# 1-Schematic_Sprinkler.net
KiCad netlist of a schematic drawn in EasyEDA
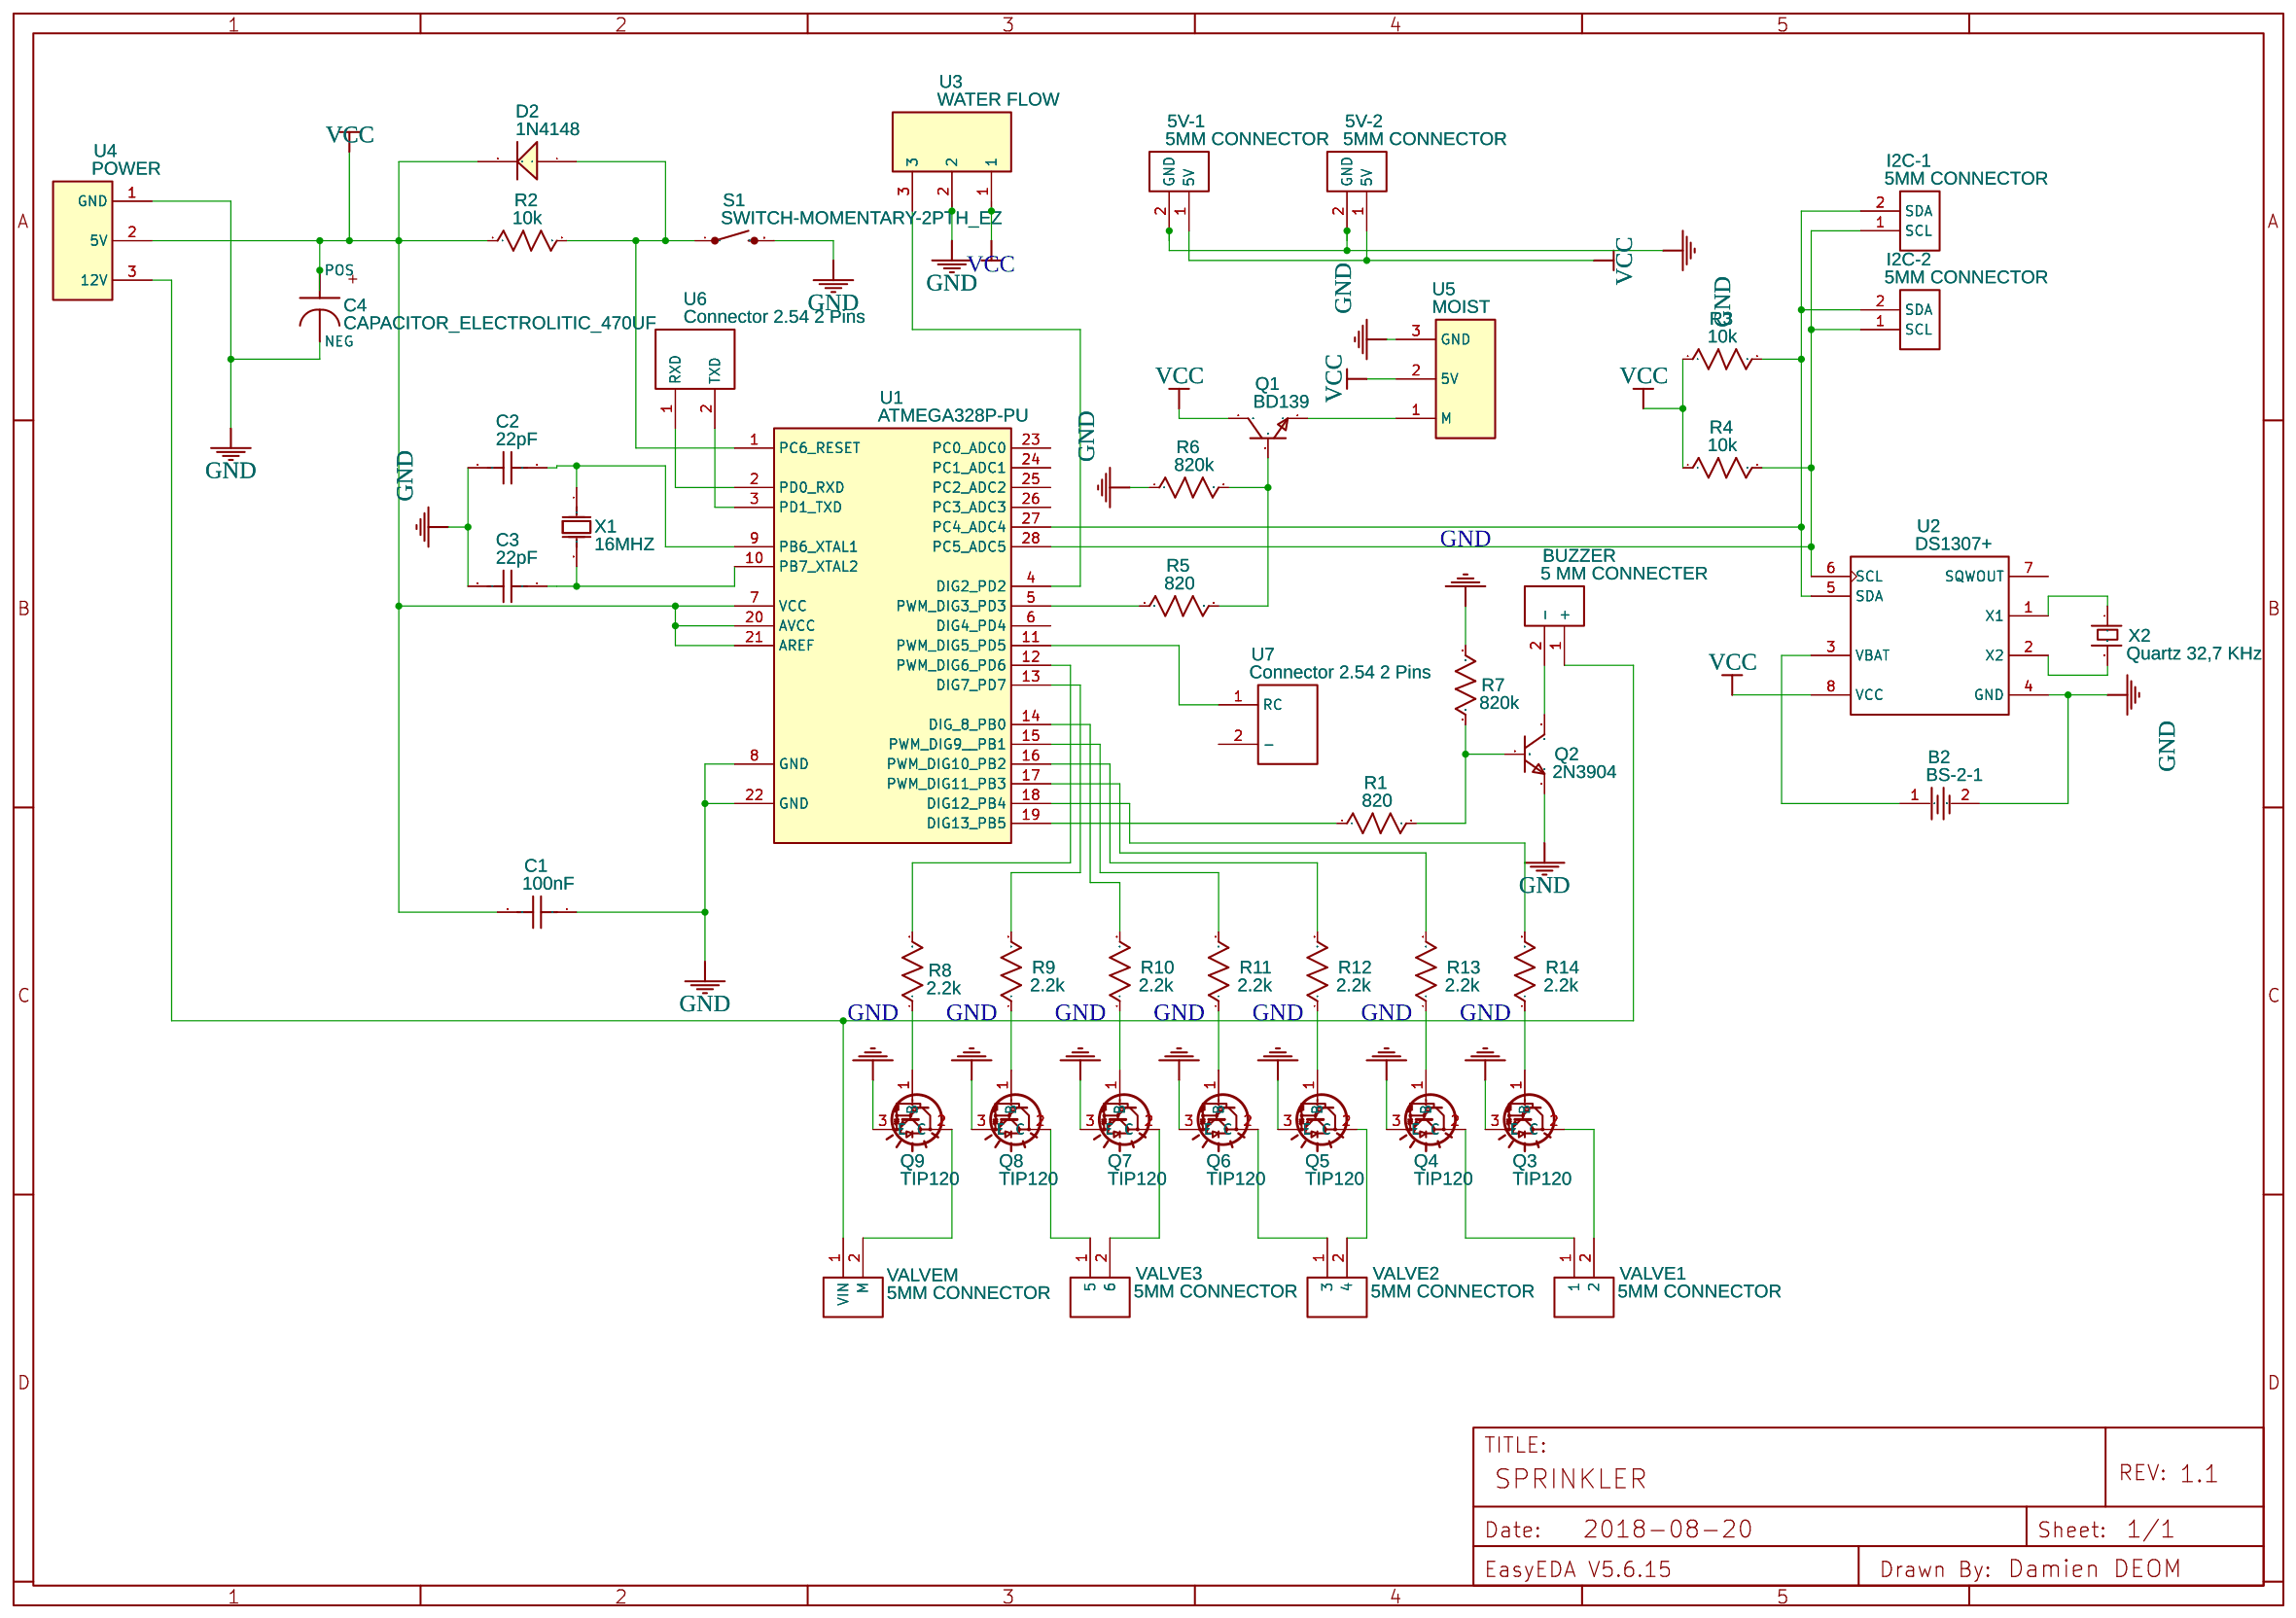
[diagram p0: schematic sheet]

(export (version "E")
  (design (tool "Eeschema 10.0.6"))
  (components
    (comp (ref "5V-1") (value "5MM CONNECTOR") (libsource (lib "") (part "Unknown_575_70")))
    (comp (ref "5V-2") (value "5MM CONNECTOR") (libsource (lib "") (part "Unknown_665_70")))
    (comp (ref "B2")
      (value "BS-2-1")
      (fields (field (name "BOM_Supplier Part") "C70376"))
      (libsource (lib "") (part "Unknown_975_400"))
    )
    (comp (ref "BUZZER")
      (value "5 MM CONNECTER")
      (fields (field (name "BOM_Manufacturer Part") "5MM CONNECTOR"))
      (libsource (lib "") (part "Unknown_765_290"))
    )
    (comp (ref "C1")
      (value "100nF")
      (fields (field (name "BOM_Manufacturer Part") "?"))
      (libsource (lib "") (part "Cap_RAD-0.1_US"))
    )
    (comp (ref "C2")
      (value "22pF")
      (fields (field (name "BOM_Manufacturer Part") "?"))
      (libsource (lib "") (part "Cap_RAD-0.1_US"))
    )
    (comp (ref "C3")
      (value "22pF")
      (fields (field (name "BOM_Manufacturer Part") "?"))
      (libsource (lib "") (part "Cap_RAD-0.1_US"))
    )
    (comp (ref "C4")
      (value "CAPACITOR_ELECTROLITIC_470UF")
      (fields (field (name "BOM_Manufacturer Part") "?"))
      (libsource (lib "") (part "Unknown_155_130"))
    )
    (comp (ref "D2")
      (value "1N4148")
      (fields (field (name "BOM_Manufacturer Part") "?"))
      (libsource (lib "") (part "Unknown_265_75"))
    )
    (comp (ref "I2C-1") (value "5MM CONNECTOR") (libsource (lib "") (part "Unknown_975_90")))
    (comp (ref "I2C-2") (value "5MM CONNECTOR") (libsource (lib "") (part "Unknown_975_140")))
    (comp (ref "Q1")
      (value "BD139")
      (fields (field (name "BOM_Supplier Part") "C27866"))
      (libsource (lib "") (part "Unknown_635_205"))
    )
    (comp (ref "Q2")
      (value "2N3904")
      (fields (field (name "BOM_Supplier Part") "C118538"))
      (libsource (lib "") (part "Unknown_765_375"))
    )
    (comp (ref "Q3")
      (value "TIP120")
      (fields (field (name "BOM_Manufacturer Part") "?"))
      (libsource (lib "") (part "Unknown_765_550"))
    )
    (comp (ref "Q4")
      (value "TIP120")
      (fields (field (name "BOM_Manufacturer Part") "?"))
      (libsource (lib "") (part "Unknown_715_550"))
    )
    (comp (ref "Q5")
      (value "TIP120")
      (fields (field (name "BOM_Manufacturer Part") "?"))
      (libsource (lib "") (part "Unknown_660_550"))
    )
    (comp (ref "Q6")
      (value "TIP120")
      (fields (field (name "BOM_Manufacturer Part") "?"))
      (libsource (lib "") (part "Unknown_610_550"))
    )
    (comp (ref "Q7")
      (value "TIP120")
      (fields (field (name "BOM_Manufacturer Part") "?"))
      (libsource (lib "") (part "Unknown_560_550"))
    )
    (comp (ref "Q8")
      (value "TIP120")
      (fields (field (name "BOM_Manufacturer Part") "?"))
      (libsource (lib "") (part "Unknown_505_550"))
    )
    (comp (ref "Q9")
      (value "TIP120")
      (fields (field (name "BOM_Manufacturer Part") "?"))
      (libsource (lib "") (part "Unknown_455_550"))
    )
    (comp (ref "R1")
      (value "820")
      (fields (field (name "BOM_Manufacturer Part") "?"))
      (libsource (lib "") (part "Res_AXIAL-0.3(1/8W)_US_1"))
    )
    (comp (ref "R2")
      (value "10k")
      (fields (field (name "BOM_Manufacturer Part") "?"))
      (libsource (lib "") (part "Res_AXIAL-0.3(1/8W)_US_1"))
    )
    (comp (ref "R3")
      (value "10k")
      (fields (field (name "BOM_Manufacturer Part") "?"))
      (libsource (lib "") (part "Res_AXIAL-0.3(1/8W)_US_1"))
    )
    (comp (ref "R4")
      (value "10k")
      (fields (field (name "BOM_Manufacturer Part") "?"))
      (libsource (lib "") (part "Res_AXIAL-0.3(1/8W)_US_1"))
    )
    (comp (ref "R5")
      (value "820")
      (fields (field (name "BOM_Manufacturer Part") "?"))
      (libsource (lib "") (part "Res_AXIAL-0.3(1/8W)_US_1"))
    )
    (comp (ref "R6")
      (value "820k")
      (fields (field (name "BOM_Manufacturer Part") "?"))
      (libsource (lib "") (part "Res_AXIAL-0.3(1/8W)_US_1"))
    )
    (comp (ref "R7")
      (value "820k")
      (fields (field (name "BOM_Manufacturer Part") "?"))
      (libsource (lib "") (part "Res_AXIAL-0.3(1/8W)_US"))
    )
    (comp (ref "R8")
      (value "2.2k")
      (fields (field (name "BOM_Manufacturer Part") "?"))
      (libsource (lib "") (part "Res_AXIAL-0.3(1/8W)_US"))
    )
    (comp (ref "R9")
      (value "2.2k")
      (fields (field (name "BOM_Manufacturer Part") "?"))
      (libsource (lib "") (part "Res_AXIAL-0.3(1/8W)_US"))
    )
    (comp (ref "R10")
      (value "2.2k")
      (fields (field (name "BOM_Manufacturer Part") "?"))
      (libsource (lib "") (part "Res_AXIAL-0.3(1/8W)_US"))
    )
    (comp (ref "R11")
      (value "2.2k")
      (fields (field (name "BOM_Manufacturer Part") "?"))
      (libsource (lib "") (part "Res_AXIAL-0.3(1/8W)_US"))
    )
    (comp (ref "R12")
      (value "2.2k")
      (fields (field (name "BOM_Manufacturer Part") "?"))
      (libsource (lib "") (part "Res_AXIAL-0.3(1/8W)_US"))
    )
    (comp (ref "R13")
      (value "2.2k")
      (fields (field (name "BOM_Manufacturer Part") "?"))
      (libsource (lib "") (part "Res_AXIAL-0.3(1/8W)_US"))
    )
    (comp (ref "R14")
      (value "2.2k")
      (fields (field (name "BOM_Manufacturer Part") "?"))
      (libsource (lib "") (part "Res_AXIAL-0.3(1/8W)_US"))
    )
    (comp (ref "S1")
      (value "SWITCH-MOMENTARY-2PTH_EZ")
      (fields (field (name "BOM_Manufacturer Part") "?"))
      (libsource (lib "") (part "Unknown_365_115"))
    )
    (comp (ref "U1")
      (value "ATMEGA328P-PU")
      (fields (field (name "BOM_Supplier Part") "C33901"))
      (libsource (lib "") (part "Unknown_425_340"))
    )
    (comp (ref "U2")
      (value "DS1307+")
      (fields (field (name "BOM_Supplier Part") "C59267"))
      (libsource (lib "") (part "Unknown_970_315"))
    )
    (comp (ref "U3")
      (value "WATER FLOW")
      (fields (field (name "BOM_Manufacturer Part") "New SchematicLib"))
      (libsource (lib "") (part "Unknown_485_110"))
    )
    (comp (ref "U4")
      (value "POWER")
      (fields (field (name "BOM_Manufacturer Part") "New SchematicLib"))
      (libsource (lib "") (part "Unknown_80_105"))
    )
    (comp (ref "U5")
      (value "MOIST")
      (fields (field (name "BOM_Manufacturer Part") "New SchematicLib"))
      (libsource (lib "") (part "Unknown_690_195"))
    )
    (comp (ref "U6")
      (value "Connector 2.54 2 Pins")
      (fields (field (name "BOM_Manufacturer Part") "New SchematicLib"))
      (libsource (lib "") (part "Unknown_345_190"))
    )
    (comp (ref "U7")
      (value "Connector 2.54 2 Pins")
      (fields (field (name "BOM_Manufacturer Part") "New SchematicLib"))
      (libsource (lib "") (part "Unknown_630_360"))
    )
    (comp (ref "VALVE1") (value "5MM CONNECTOR") (libsource (lib "") (part "Unknown_810_660")))
    (comp (ref "VALVE2") (value "5MM CONNECTOR") (libsource (lib "") (part "Unknown_685_660")))
    (comp (ref "VALVE3") (value "5MM CONNECTOR") (libsource (lib "") (part "Unknown_565_660")))
    (comp (ref "VALVEM") (value "5MM CONNECTOR") (libsource (lib "") (part "Unknown_440_660")))
    (comp (ref "X1")
      (value "16MHZ")
      (fields
        (field (name "BOM_Manufacturer Part") "X49SD16MSD2SC")
        (field (name "BOM_Supplier Part") "C16212")
      )
      (libsource (lib "") (part "Unknown_285_260"))
    )
    (comp (ref "X2")
      (value "Quartz 32,7 KHz")
      (fields (field (name "BOM_Manufacturer Part") "?"))
      (libsource (lib "") (part "Unknown_1060_315"))
    )
  )
  (nets
    (net (code "1") (name "GND") (class "Default")
      (node (ref "5V-1") (pin "2") (pinfunction "GND_2") (pintype "unspecified"))
      (node (ref "5V-2") (pin "2") (pinfunction "GND_2") (pintype "unspecified"))
      (node (ref "B2") (pin "2") (pinfunction "2_2") (pintype "input"))
      (node (ref "C1") (pin "1") (pinfunction "1_1") (pintype "unspecified"))
      (node (ref "C2") (pin "2") (pinfunction "2_2") (pintype "unspecified"))
      (node (ref "C3") (pin "2") (pinfunction "2_2") (pintype "unspecified"))
      (node (ref "C4") (pin "NEG") (pinfunction "NEG_NEG") (pintype "bidirectional"))
      (node (ref "Q2") (pin "1") (pinfunction "E_1") (pintype "unspecified"))
      (node (ref "Q3") (pin "3") (pinfunction "E_3") (pintype "unspecified"))
      (node (ref "Q4") (pin "3") (pinfunction "E_3") (pintype "unspecified"))
      (node (ref "Q5") (pin "3") (pinfunction "E_3") (pintype "unspecified"))
      (node (ref "Q6") (pin "3") (pinfunction "E_3") (pintype "unspecified"))
      (node (ref "Q7") (pin "3") (pinfunction "E_3") (pintype "unspecified"))
      (node (ref "Q8") (pin "3") (pinfunction "E_3") (pintype "unspecified"))
      (node (ref "Q9") (pin "3") (pinfunction "E_3") (pintype "unspecified"))
      (node (ref "R6") (pin "1") (pinfunction "1_1") (pintype "unspecified"))
      (node (ref "R7") (pin "2") (pinfunction "2_2") (pintype "unspecified"))
      (node (ref "S1") (pin "3") (pinfunction "2_3") (pintype "unspecified"))
      (node (ref "U1") (pin "22") (pinfunction "GND_22") (pintype "passive"))
      (node (ref "U1") (pin "8") (pinfunction "GND_8") (pintype "passive"))
      (node (ref "U2") (pin "4") (pinfunction "GND_4") (pintype "passive"))
      (node (ref "U3") (pin "2") (pinfunction "2_2") (pintype "input"))
      (node (ref "U4") (pin "1") (pinfunction "GND_1") (pintype "input"))
      (node (ref "U5") (pin "3") (pinfunction "GND_3") (pintype "input"))
    )
    (net (code "2") (name "Net-(BUZZER-+)") (class "Default")
      (node (ref "BUZZER") (pin "1") (pinfunction "+_1") (pintype "unspecified"))
      (node (ref "U4") (pin "3") (pinfunction "12V_3") (pintype "input"))
      (node (ref "VALVEM") (pin "1") (pinfunction "VIN_1") (pintype "unspecified"))
    )
    (net (code "3") (name "Net-(BUZZER--)") (class "Default")
      (node (ref "BUZZER") (pin "2") (pinfunction "-_2") (pintype "unspecified"))
      (node (ref "Q2") (pin "3") (pinfunction "C_3") (pintype "unspecified"))
    )
    (net (code "4") (name "Net-(D2-A)") (class "Default")
      (node (ref "D2") (pin "1") (pinfunction "A_1") (pintype "unspecified"))
      (node (ref "R2") (pin "2") (pinfunction "2_2") (pintype "unspecified"))
      (node (ref "S1") (pin "1") (pinfunction "1_1") (pintype "unspecified"))
      (node (ref "U1") (pin "1") (pinfunction "PC6_RESET_1") (pintype "bidirectional"))
    )
    (net (code "5") (name "Net-(I2C-1-SCL)") (class "Default")
      (node (ref "I2C-1") (pin "1") (pinfunction "SCL_1") (pintype "unspecified"))
      (node (ref "I2C-2") (pin "1") (pinfunction "SCL_1") (pintype "unspecified"))
      (node (ref "R4") (pin "2") (pinfunction "2_2") (pintype "unspecified"))
      (node (ref "U1") (pin "28") (pinfunction "PC5_ADC5_28") (pintype "bidirectional"))
      (node (ref "U2") (pin "6") (pinfunction "SCL_6") (pintype "unspecified"))
    )
    (net (code "6") (name "Net-(I2C-1-SDA)") (class "Default")
      (node (ref "I2C-1") (pin "2") (pinfunction "SDA_2") (pintype "unspecified"))
      (node (ref "I2C-2") (pin "2") (pinfunction "SDA_2") (pintype "unspecified"))
      (node (ref "R3") (pin "2") (pinfunction "2_2") (pintype "unspecified"))
      (node (ref "U1") (pin "27") (pinfunction "PC4_ADC4_27") (pintype "bidirectional"))
      (node (ref "U2") (pin "5") (pinfunction "SDA_5") (pintype "bidirectional"))
    )
    (net (code "7") (name "Net-(Q1-B)") (class "Default")
      (node (ref "Q1") (pin "1") (pinfunction "B_1") (pintype "unspecified"))
      (node (ref "R5") (pin "2") (pinfunction "2_2") (pintype "unspecified"))
      (node (ref "R6") (pin "2") (pinfunction "2_2") (pintype "unspecified"))
    )
    (net (code "8") (name "Net-(Q1-E)") (class "Default")
      (node (ref "Q1") (pin "3") (pinfunction "E_3") (pintype "unspecified"))
      (node (ref "U5") (pin "1") (pinfunction "M_1") (pintype "input"))
    )
    (net (code "9") (name "Net-(Q2-B)") (class "Default")
      (node (ref "Q2") (pin "2") (pinfunction "B_2") (pintype "unspecified"))
      (node (ref "R1") (pin "2") (pinfunction "2_2") (pintype "unspecified"))
      (node (ref "R7") (pin "1") (pinfunction "1_1") (pintype "unspecified"))
    )
    (net (code "10") (name "Net-(Q3-B)") (class "Default")
      (node (ref "Q3") (pin "1") (pinfunction "B_1") (pintype "input"))
      (node (ref "R14") (pin "1") (pinfunction "1_1") (pintype "unspecified"))
    )
    (net (code "11") (name "Net-(Q3-C)") (class "Default")
      (node (ref "Q3") (pin "2") (pinfunction "C_2") (pintype "unspecified"))
      (node (ref "VALVE1") (pin "2") (pinfunction "2_2") (pintype "unspecified"))
    )
    (net (code "12") (name "Net-(Q4-B)") (class "Default")
      (node (ref "Q4") (pin "1") (pinfunction "B_1") (pintype "input"))
      (node (ref "R13") (pin "1") (pinfunction "1_1") (pintype "unspecified"))
    )
    (net (code "13") (name "Net-(Q4-C)") (class "Default")
      (node (ref "Q4") (pin "2") (pinfunction "C_2") (pintype "unspecified"))
      (node (ref "VALVE1") (pin "1") (pinfunction "1_1") (pintype "unspecified"))
    )
    (net (code "14") (name "Net-(Q5-B)") (class "Default")
      (node (ref "Q5") (pin "1") (pinfunction "B_1") (pintype "input"))
      (node (ref "R12") (pin "1") (pinfunction "1_1") (pintype "unspecified"))
    )
    (net (code "15") (name "Net-(Q5-C)") (class "Default")
      (node (ref "Q5") (pin "2") (pinfunction "C_2") (pintype "unspecified"))
      (node (ref "VALVE2") (pin "2") (pinfunction "4_2") (pintype "unspecified"))
    )
    (net (code "16") (name "Net-(Q6-B)") (class "Default")
      (node (ref "Q6") (pin "1") (pinfunction "B_1") (pintype "input"))
      (node (ref "R11") (pin "1") (pinfunction "1_1") (pintype "unspecified"))
    )
    (net (code "17") (name "Net-(Q6-C)") (class "Default")
      (node (ref "Q6") (pin "2") (pinfunction "C_2") (pintype "unspecified"))
      (node (ref "VALVE2") (pin "1") (pinfunction "3_1") (pintype "unspecified"))
    )
    (net (code "18") (name "Net-(Q7-B)") (class "Default")
      (node (ref "Q7") (pin "1") (pinfunction "B_1") (pintype "input"))
      (node (ref "R10") (pin "1") (pinfunction "1_1") (pintype "unspecified"))
    )
    (net (code "19") (name "Net-(Q7-C)") (class "Default")
      (node (ref "Q7") (pin "2") (pinfunction "C_2") (pintype "unspecified"))
      (node (ref "VALVE3") (pin "2") (pinfunction "6_2") (pintype "unspecified"))
    )
    (net (code "20") (name "Net-(Q8-B)") (class "Default")
      (node (ref "Q8") (pin "1") (pinfunction "B_1") (pintype "input"))
      (node (ref "R9") (pin "1") (pinfunction "1_1") (pintype "unspecified"))
    )
    (net (code "21") (name "Net-(Q8-C)") (class "Default")
      (node (ref "Q8") (pin "2") (pinfunction "C_2") (pintype "unspecified"))
      (node (ref "VALVE3") (pin "1") (pinfunction "5_1") (pintype "unspecified"))
    )
    (net (code "22") (name "Net-(Q9-B)") (class "Default")
      (node (ref "Q9") (pin "1") (pinfunction "B_1") (pintype "input"))
      (node (ref "R8") (pin "1") (pinfunction "1_1") (pintype "unspecified"))
    )
    (net (code "23") (name "Net-(Q9-C)") (class "Default")
      (node (ref "Q9") (pin "2") (pinfunction "C_2") (pintype "unspecified"))
      (node (ref "VALVEM") (pin "2") (pinfunction "M_2") (pintype "unspecified"))
    )
    (net (code "24") (name "Net-(U1-DIG2_PD2)") (class "Default")
      (node (ref "U1") (pin "4") (pinfunction "DIG2_PD2_4") (pintype "bidirectional"))
      (node (ref "U3") (pin "3") (pinfunction "3_3") (pintype "input"))
    )
    (net (code "25") (name "Net-(U1-DIG7_PD7)") (class "Default")
      (node (ref "R9") (pin "2") (pinfunction "2_2") (pintype "unspecified"))
      (node (ref "U1") (pin "13") (pinfunction "DIG7_PD7_13") (pintype "bidirectional"))
    )
    (net (code "26") (name "Net-(U1-DIG12_PB4)") (class "Default")
      (node (ref "R14") (pin "2") (pinfunction "2_2") (pintype "unspecified"))
      (node (ref "U1") (pin "18") (pinfunction "DIG12_PB4_18") (pintype "bidirectional"))
    )
    (net (code "27") (name "Net-(U1-DIG13_PB5)") (class "Default")
      (node (ref "R1") (pin "1") (pinfunction "1_1") (pintype "unspecified"))
      (node (ref "U1") (pin "19") (pinfunction "DIG13_PB5_19") (pintype "bidirectional"))
    )
    (net (code "28") (name "Net-(U1-DIG_8_PB0)") (class "Default")
      (node (ref "R10") (pin "2") (pinfunction "2_2") (pintype "unspecified"))
      (node (ref "U1") (pin "14") (pinfunction "DIG_8_PB0_14") (pintype "bidirectional"))
    )
    (net (code "29") (name "Net-(U1-PB6_XTAL1)") (class "Default")
      (node (ref "C2") (pin "1") (pinfunction "1_1") (pintype "unspecified"))
      (node (ref "U1") (pin "9") (pinfunction "PB6_XTAL1_9") (pintype "bidirectional"))
      (node (ref "X1") (pin "1") (pinfunction "OSC1_1") (pintype "input"))
    )
    (net (code "30") (name "Net-(U1-PB7_XTAL2)") (class "Default")
      (node (ref "C3") (pin "1") (pinfunction "1_1") (pintype "unspecified"))
      (node (ref "U1") (pin "10") (pinfunction "PB7_XTAL2_10") (pintype "bidirectional"))
      (node (ref "X1") (pin "2") (pinfunction "OSC2_2") (pintype "input"))
    )
    (net (code "31") (name "Net-(U1-PD0_RXD)") (class "Default")
      (node (ref "U1") (pin "2") (pinfunction "PD0_RXD_2") (pintype "bidirectional"))
      (node (ref "U6") (pin "1") (pinfunction "RXD_1") (pintype "unspecified"))
    )
    (net (code "32") (name "Net-(U1-PD1_TXD)") (class "Default")
      (node (ref "U1") (pin "3") (pinfunction "PD1_TXD_3") (pintype "bidirectional"))
      (node (ref "U6") (pin "2") (pinfunction "TXD_2") (pintype "unspecified"))
    )
    (net (code "33") (name "Net-(U1-PWM_DIG3_PD3)") (class "Default")
      (node (ref "R5") (pin "1") (pinfunction "1_1") (pintype "unspecified"))
      (node (ref "U1") (pin "5") (pinfunction "PWM_DIG3_PD3_5") (pintype "bidirectional"))
    )
    (net (code "34") (name "Net-(U1-PWM_DIG5_PD5)") (class "Default")
      (node (ref "U1") (pin "11") (pinfunction "PWM_DIG5_PD5_11") (pintype "bidirectional"))
      (node (ref "U7") (pin "1") (pinfunction "RC_1") (pintype "unspecified"))
    )
    (net (code "35") (name "Net-(U1-PWM_DIG6_PD6)") (class "Default")
      (node (ref "R8") (pin "2") (pinfunction "2_2") (pintype "unspecified"))
      (node (ref "U1") (pin "12") (pinfunction "PWM_DIG6_PD6_12") (pintype "bidirectional"))
    )
    (net (code "36") (name "Net-(U1-PWM_DIG9__PB1)") (class "Default")
      (node (ref "R11") (pin "2") (pinfunction "2_2") (pintype "unspecified"))
      (node (ref "U1") (pin "15") (pinfunction "PWM_DIG9__PB1_15") (pintype "bidirectional"))
    )
    (net (code "37") (name "Net-(U1-PWM_DIG10_PB2)") (class "Default")
      (node (ref "R12") (pin "2") (pinfunction "2_2") (pintype "unspecified"))
      (node (ref "U1") (pin "16") (pinfunction "PWM_DIG10_PB2_16") (pintype "bidirectional"))
    )
    (net (code "38") (name "Net-(U1-PWM_DIG11_PB3)") (class "Default")
      (node (ref "R13") (pin "2") (pinfunction "2_2") (pintype "unspecified"))
      (node (ref "U1") (pin "17") (pinfunction "PWM_DIG11_PB3_17") (pintype "bidirectional"))
    )
    (net (code "39") (name "Net-(U2-VBAT)") (class "Default")
      (node (ref "B2") (pin "1") (pinfunction "1_1") (pintype "input"))
      (node (ref "U2") (pin "3") (pinfunction "VBAT_3") (pintype "passive"))
    )
    (net (code "40") (name "Net-(U2-X1)") (class "Default")
      (node (ref "U2") (pin "1") (pinfunction "X1_1") (pintype "unspecified"))
      (node (ref "X2") (pin "1") (pinfunction "1_1") (pintype "unspecified"))
    )
    (net (code "41") (name "Net-(U2-X2)") (class "Default")
      (node (ref "U2") (pin "2") (pinfunction "X2_2") (pintype "unspecified"))
      (node (ref "X2") (pin "2") (pinfunction "2_2") (pintype "unspecified"))
    )
    (net (code "42") (name "VCC") (class "Default")
      (node (ref "5V-1") (pin "1") (pinfunction "5V_1") (pintype "unspecified"))
      (node (ref "5V-2") (pin "1") (pinfunction "5V_1") (pintype "unspecified"))
      (node (ref "C1") (pin "2") (pinfunction "2_2") (pintype "unspecified"))
      (node (ref "C4") (pin "POS") (pinfunction "POS_POS") (pintype "bidirectional"))
      (node (ref "D2") (pin "2") (pinfunction "K_2") (pintype "unspecified"))
      (node (ref "Q1") (pin "2") (pinfunction "C_2") (pintype "unspecified"))
      (node (ref "R2") (pin "1") (pinfunction "1_1") (pintype "unspecified"))
      (node (ref "R3") (pin "1") (pinfunction "1_1") (pintype "unspecified"))
      (node (ref "R4") (pin "1") (pinfunction "1_1") (pintype "unspecified"))
      (node (ref "U1") (pin "20") (pinfunction "AVCC_20") (pintype "passive"))
      (node (ref "U1") (pin "21") (pinfunction "AREF_21") (pintype "passive"))
      (node (ref "U1") (pin "7") (pinfunction "VCC_7") (pintype "passive"))
      (node (ref "U2") (pin "8") (pinfunction "VCC_8") (pintype "passive"))
      (node (ref "U3") (pin "1") (pinfunction "1_1") (pintype "input"))
      (node (ref "U4") (pin "2") (pinfunction "5V_2") (pintype "input"))
      (node (ref "U5") (pin "2") (pinfunction "5V_2") (pintype "input"))
    )
    (net (code "43") (name "unconnected-(U1-DIG4_PD4-Pad6)") (class "Default")
      (node (ref "U1") (pin "6") (pinfunction "DIG4_PD4_6") (pintype "bidirectional"))
    )
    (net (code "44") (name "unconnected-(U1-PC0_ADC0-Pad23)") (class "Default")
      (node (ref "U1") (pin "23") (pinfunction "PC0_ADC0_23") (pintype "bidirectional"))
    )
    (net (code "45") (name "unconnected-(U1-PC1_ADC1-Pad24)") (class "Default")
      (node (ref "U1") (pin "24") (pinfunction "PC1_ADC1_24") (pintype "bidirectional"))
    )
    (net (code "46") (name "unconnected-(U1-PC2_ADC2-Pad25)") (class "Default")
      (node (ref "U1") (pin "25") (pinfunction "PC2_ADC2_25") (pintype "bidirectional"))
    )
    (net (code "47") (name "unconnected-(U1-PC3_ADC3-Pad26)") (class "Default")
      (node (ref "U1") (pin "26") (pinfunction "PC3_ADC3_26") (pintype "bidirectional"))
    )
    (net (code "48") (name "unconnected-(U2-SQWOUT-Pad7)") (class "Default")
      (node (ref "U2") (pin "7") (pinfunction "SQWOUT_7") (pintype "unspecified"))
    )
    (net (code "49") (name "unconnected-(U7---Pad2)") (class "Default")
      (node (ref "U7") (pin "2") (pinfunction "-_2") (pintype "unspecified"))
    )
  )
)
